# LEDSlave_4.net
KiCad netlist of a schematic drawn in EAGLE
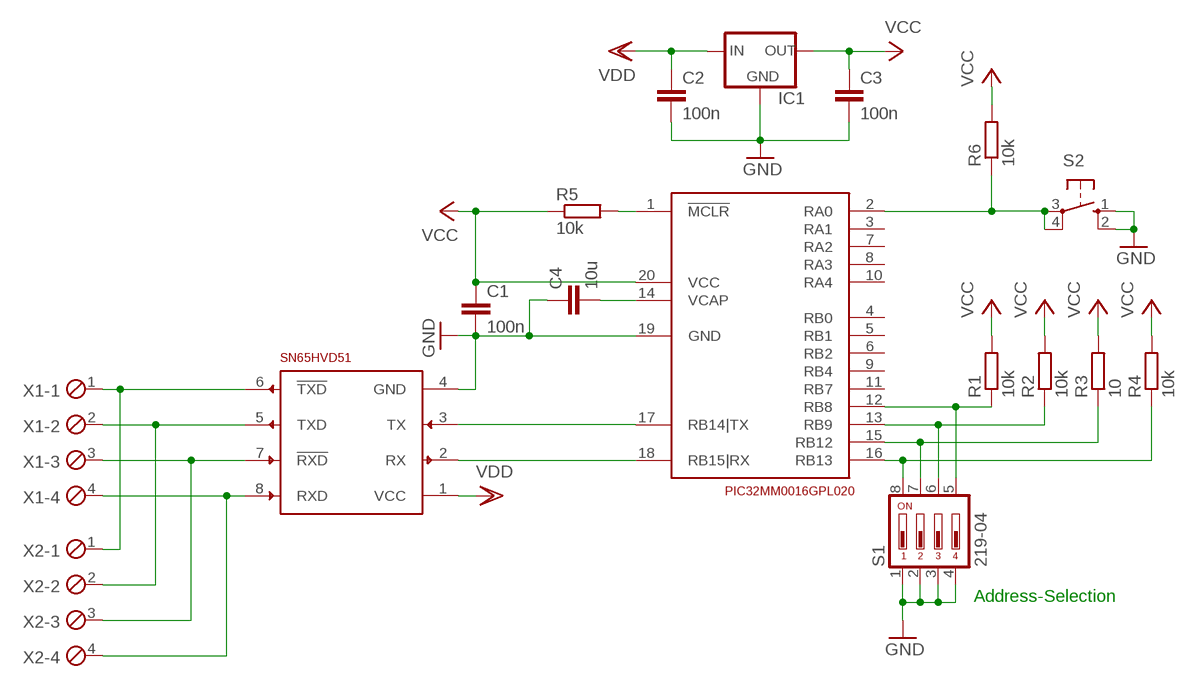
[diagram p0: schematic, sheet 1]

(export (version "E")
  (design (tool "Eeschema 10.0.6"))
  (components
    (comp (ref "C1")
      (value "100n")
      (footprint "eagle-import:C0805")
      (libsource (lib "eagle-import") (part "C-EUC0805"))
    )
    (comp (ref "C2")
      (value "100n")
      (footprint "eagle-import:C0805")
      (libsource (lib "eagle-import") (part "C-EUC0805"))
    )
    (comp (ref "C3")
      (value "100n")
      (footprint "eagle-import:C0805")
      (libsource (lib "eagle-import") (part "C-EUC0805"))
    )
    (comp (ref "C4")
      (value "10u")
      (footprint "eagle-import:C1206")
      (libsource (lib "eagle-import") (part "C-EUC1206"))
    )
    (comp (ref "IC1")
      (value "LP2950CDT-3.3")
      (footprint "eagle-import:DPACK")
      (libsource (lib "eagle-import") (part "LP2950?CDT-3.3"))
    )
    (comp (ref "R1")
      (value "10k")
      (footprint "eagle-import:R0805")
      (libsource (lib "eagle-import") (part "R-EU_R0805"))
    )
    (comp (ref "R2")
      (value "10k")
      (footprint "eagle-import:R0805")
      (libsource (lib "eagle-import") (part "R-EU_R0805"))
    )
    (comp (ref "R3")
      (value "10")
      (footprint "eagle-import:R0805")
      (libsource (lib "eagle-import") (part "R-EU_R0805"))
    )
    (comp (ref "R4")
      (value "10k")
      (footprint "eagle-import:R0805")
      (libsource (lib "eagle-import") (part "R-EU_R0805"))
    )
    (comp (ref "R5")
      (value "10k")
      (footprint "eagle-import:R0805")
      (libsource (lib "eagle-import") (part "R-EU_R0805"))
    )
    (comp (ref "R6")
      (value "10k")
      (footprint "eagle-import:R0805")
      (libsource (lib "eagle-import") (part "R-EU_R0805"))
    )
    (comp (ref "S1")
      (value "219-04")
      (footprint "eagle-import:CTS-219-04")
      (libsource (lib "eagle-import") (part "219-04"))
    )
    (comp (ref "S2")
      (value "10-XX")
      (footprint "eagle-import:B3F-10XX")
      (fields (field (name "MPN") "B3F-1000"))
      (libsource (lib "eagle-import") (part "10-XX"))
    )
    (comp (ref "U$1")
      (value "PIC32MM0016GPL020")
      (footprint "eagle-import:SSOP20")
      (libsource (lib "eagle-import") (part "PIC32MM0016GPL020"))
    )
    (comp (ref "U$2")
      (value "SN65HVD51")
      (footprint "eagle-import:SO-08")
      (libsource (lib "eagle-import") (part "SN65HVD51"))
    )
    (comp (ref "X1")
      (value "MPT4")
      (footprint "eagle-import:4POL254")
      (libsource (lib "eagle-import") (part "MPT4"))
    )
    (comp (ref "X2")
      (value "MPT4")
      (footprint "eagle-import:4POL254")
      (libsource (lib "eagle-import") (part "MPT4"))
    )
  )
  (nets
    (net (code "1") (name "GND") (class "Default")
      (node (ref "C1") (pin "2") (pinfunction "2_2") (pintype "passive"))
      (node (ref "C2") (pin "2") (pinfunction "2_2") (pintype "passive"))
      (node (ref "C3") (pin "2") (pinfunction "2_2") (pintype "passive"))
      (node (ref "C4") (pin "1") (pinfunction "1_1") (pintype "passive"))
      (node (ref "IC1") (pin "4") (pinfunction "GND_4") (pintype "input"))
      (node (ref "S1") (pin "1") (pinfunction "1_1") (pintype "passive"))
      (node (ref "S1") (pin "2") (pinfunction "2_2") (pintype "passive"))
      (node (ref "S1") (pin "3") (pinfunction "3_3") (pintype "passive"))
      (node (ref "S1") (pin "4") (pinfunction "4_4") (pintype "passive"))
      (node (ref "S2") (pin "1") (pinfunction "S_1") (pintype "passive"))
      (node (ref "S2") (pin "2") (pinfunction "S1_2") (pintype "passive"))
      (node (ref "U$1") (pin "19") (pinfunction "GND_19") (pintype "bidirectional"))
      (node (ref "U$2") (pin "4") (pinfunction "GND_4") (pintype "bidirectional"))
    )
    (net (code "2") (name "Net-(S2-P)") (class "Default")
      (node (ref "R6") (pin "1") (pinfunction "1_1") (pintype "passive"))
      (node (ref "S2") (pin "3") (pinfunction "P_3") (pintype "passive"))
      (node (ref "S2") (pin "4") (pinfunction "P1_4") (pintype "passive"))
      (node (ref "U$1") (pin "2") (pinfunction "RA0_2") (pintype "bidirectional"))
    )
    (net (code "3") (name "Net-(U$1-RB8)") (class "Default")
      (node (ref "R1") (pin "1") (pinfunction "1_1") (pintype "passive"))
      (node (ref "S1") (pin "5") (pinfunction "5_5") (pintype "passive"))
      (node (ref "U$1") (pin "12") (pinfunction "RB8_12") (pintype "bidirectional"))
    )
    (net (code "4") (name "Net-(U$1-RB9)") (class "Default")
      (node (ref "R2") (pin "1") (pinfunction "1_1") (pintype "passive"))
      (node (ref "S1") (pin "6") (pinfunction "6_6") (pintype "passive"))
      (node (ref "U$1") (pin "13") (pinfunction "RB9_13") (pintype "bidirectional"))
    )
    (net (code "5") (name "Net-(U$1-RB12)") (class "Default")
      (node (ref "R3") (pin "1") (pinfunction "1_1") (pintype "passive"))
      (node (ref "S1") (pin "7") (pinfunction "7_7") (pintype "passive"))
      (node (ref "U$1") (pin "15") (pinfunction "RB12_15") (pintype "bidirectional"))
    )
    (net (code "6") (name "Net-(U$1-RB13)") (class "Default")
      (node (ref "R4") (pin "1") (pinfunction "1_1") (pintype "passive"))
      (node (ref "S1") (pin "8") (pinfunction "8_8") (pintype "passive"))
      (node (ref "U$1") (pin "16") (pinfunction "RB13_16") (pintype "bidirectional"))
    )
    (net (code "7") (name "Net-(U$1-RB14|TX)") (class "Default")
      (node (ref "U$1") (pin "17") (pinfunction "RB14|TX_17") (pintype "bidirectional"))
      (node (ref "U$2") (pin "3") (pinfunction "TX_3") (pintype "bidirectional"))
    )
    (net (code "8") (name "Net-(U$1-RB15|RX)") (class "Default")
      (node (ref "U$1") (pin "18") (pinfunction "RB15|RX_18") (pintype "bidirectional"))
      (node (ref "U$2") (pin "2") (pinfunction "RX_2") (pintype "bidirectional"))
    )
    (net (code "9") (name "Net-(U$1-VCAP)") (class "Default")
      (node (ref "C4") (pin "2") (pinfunction "2_2") (pintype "passive"))
      (node (ref "U$1") (pin "14") (pinfunction "VCAP_14") (pintype "bidirectional"))
    )
    (net (code "10") (name "Net-(U$1-~{MCLR})") (class "Default")
      (node (ref "R5") (pin "2") (pinfunction "2_2") (pintype "passive"))
      (node (ref "U$1") (pin "1") (pinfunction "~{MCLR}_1") (pintype "bidirectional"))
    )
    (net (code "11") (name "Net-(U$2-RXD)") (class "Default")
      (node (ref "U$2") (pin "8") (pinfunction "RXD_8") (pintype "bidirectional"))
      (node (ref "X1") (pin "4") (pinfunction "1_4") (pintype "passive"))
      (node (ref "X2") (pin "4") (pinfunction "1_4") (pintype "passive"))
    )
    (net (code "12") (name "Net-(U$2-TXD)") (class "Default")
      (node (ref "U$2") (pin "5") (pinfunction "TXD_5") (pintype "bidirectional"))
      (node (ref "X1") (pin "2") (pinfunction "1_2") (pintype "passive"))
      (node (ref "X2") (pin "2") (pinfunction "1_2") (pintype "passive"))
    )
    (net (code "13") (name "Net-(U$2-~{RXD})") (class "Default")
      (node (ref "U$2") (pin "7") (pinfunction "~{RXD}_7") (pintype "bidirectional"))
      (node (ref "X1") (pin "3") (pinfunction "1_3") (pintype "passive"))
      (node (ref "X2") (pin "3") (pinfunction "1_3") (pintype "passive"))
    )
    (net (code "14") (name "Net-(U$2-~{TXD})") (class "Default")
      (node (ref "U$2") (pin "6") (pinfunction "~{TXD}_6") (pintype "bidirectional"))
      (node (ref "X1") (pin "1") (pinfunction "1_1") (pintype "passive"))
      (node (ref "X2") (pin "1") (pinfunction "1_1") (pintype "passive"))
    )
    (net (code "15") (name "VCC") (class "Default")
      (node (ref "C1") (pin "1") (pinfunction "1_1") (pintype "passive"))
      (node (ref "C3") (pin "1") (pinfunction "1_1") (pintype "passive"))
      (node (ref "IC1") (pin "3") (pinfunction "OUT_3") (pintype "passive"))
      (node (ref "R1") (pin "2") (pinfunction "2_2") (pintype "passive"))
      (node (ref "R2") (pin "2") (pinfunction "2_2") (pintype "passive"))
      (node (ref "R3") (pin "2") (pinfunction "2_2") (pintype "passive"))
      (node (ref "R4") (pin "2") (pinfunction "2_2") (pintype "passive"))
      (node (ref "R5") (pin "1") (pinfunction "1_1") (pintype "passive"))
      (node (ref "R6") (pin "2") (pinfunction "2_2") (pintype "passive"))
      (node (ref "U$1") (pin "20") (pinfunction "VCC_20") (pintype "bidirectional"))
    )
    (net (code "16") (name "VDD") (class "Default")
      (node (ref "C2") (pin "1") (pinfunction "1_1") (pintype "passive"))
      (node (ref "IC1") (pin "1") (pinfunction "IN_1") (pintype "input"))
      (node (ref "U$2") (pin "1") (pinfunction "VCC_1") (pintype "bidirectional"))
    )
    (net (code "17") (name "unconnected-(U$1-RA1-Pad3)") (class "Default")
      (node (ref "U$1") (pin "3") (pinfunction "RA1_3") (pintype "bidirectional"))
    )
    (net (code "18") (name "unconnected-(U$1-RA2-Pad7)") (class "Default")
      (node (ref "U$1") (pin "7") (pinfunction "RA2_7") (pintype "bidirectional"))
    )
    (net (code "19") (name "unconnected-(U$1-RA3-Pad8)") (class "Default")
      (node (ref "U$1") (pin "8") (pinfunction "RA3_8") (pintype "bidirectional"))
    )
    (net (code "20") (name "unconnected-(U$1-RA4-Pad10)") (class "Default")
      (node (ref "U$1") (pin "10") (pinfunction "RA4_10") (pintype "bidirectional"))
    )
    (net (code "21") (name "unconnected-(U$1-RB0-Pad4)") (class "Default")
      (node (ref "U$1") (pin "4") (pinfunction "RB0_4") (pintype "bidirectional"))
    )
    (net (code "22") (name "unconnected-(U$1-RB1-Pad5)") (class "Default")
      (node (ref "U$1") (pin "5") (pinfunction "RB1_5") (pintype "bidirectional"))
    )
    (net (code "23") (name "unconnected-(U$1-RB2-Pad6)") (class "Default")
      (node (ref "U$1") (pin "6") (pinfunction "RB2_6") (pintype "bidirectional"))
    )
    (net (code "24") (name "unconnected-(U$1-RB4-Pad9)") (class "Default")
      (node (ref "U$1") (pin "9") (pinfunction "RB4_9") (pintype "bidirectional"))
    )
    (net (code "25") (name "unconnected-(U$1-RB7-Pad11)") (class "Default")
      (node (ref "U$1") (pin "11") (pinfunction "RB7_11") (pintype "bidirectional"))
    )
  )
)
